# Trampoline_Sensor_Breakout.net
KiCad netlist of a schematic drawn in EAGLE
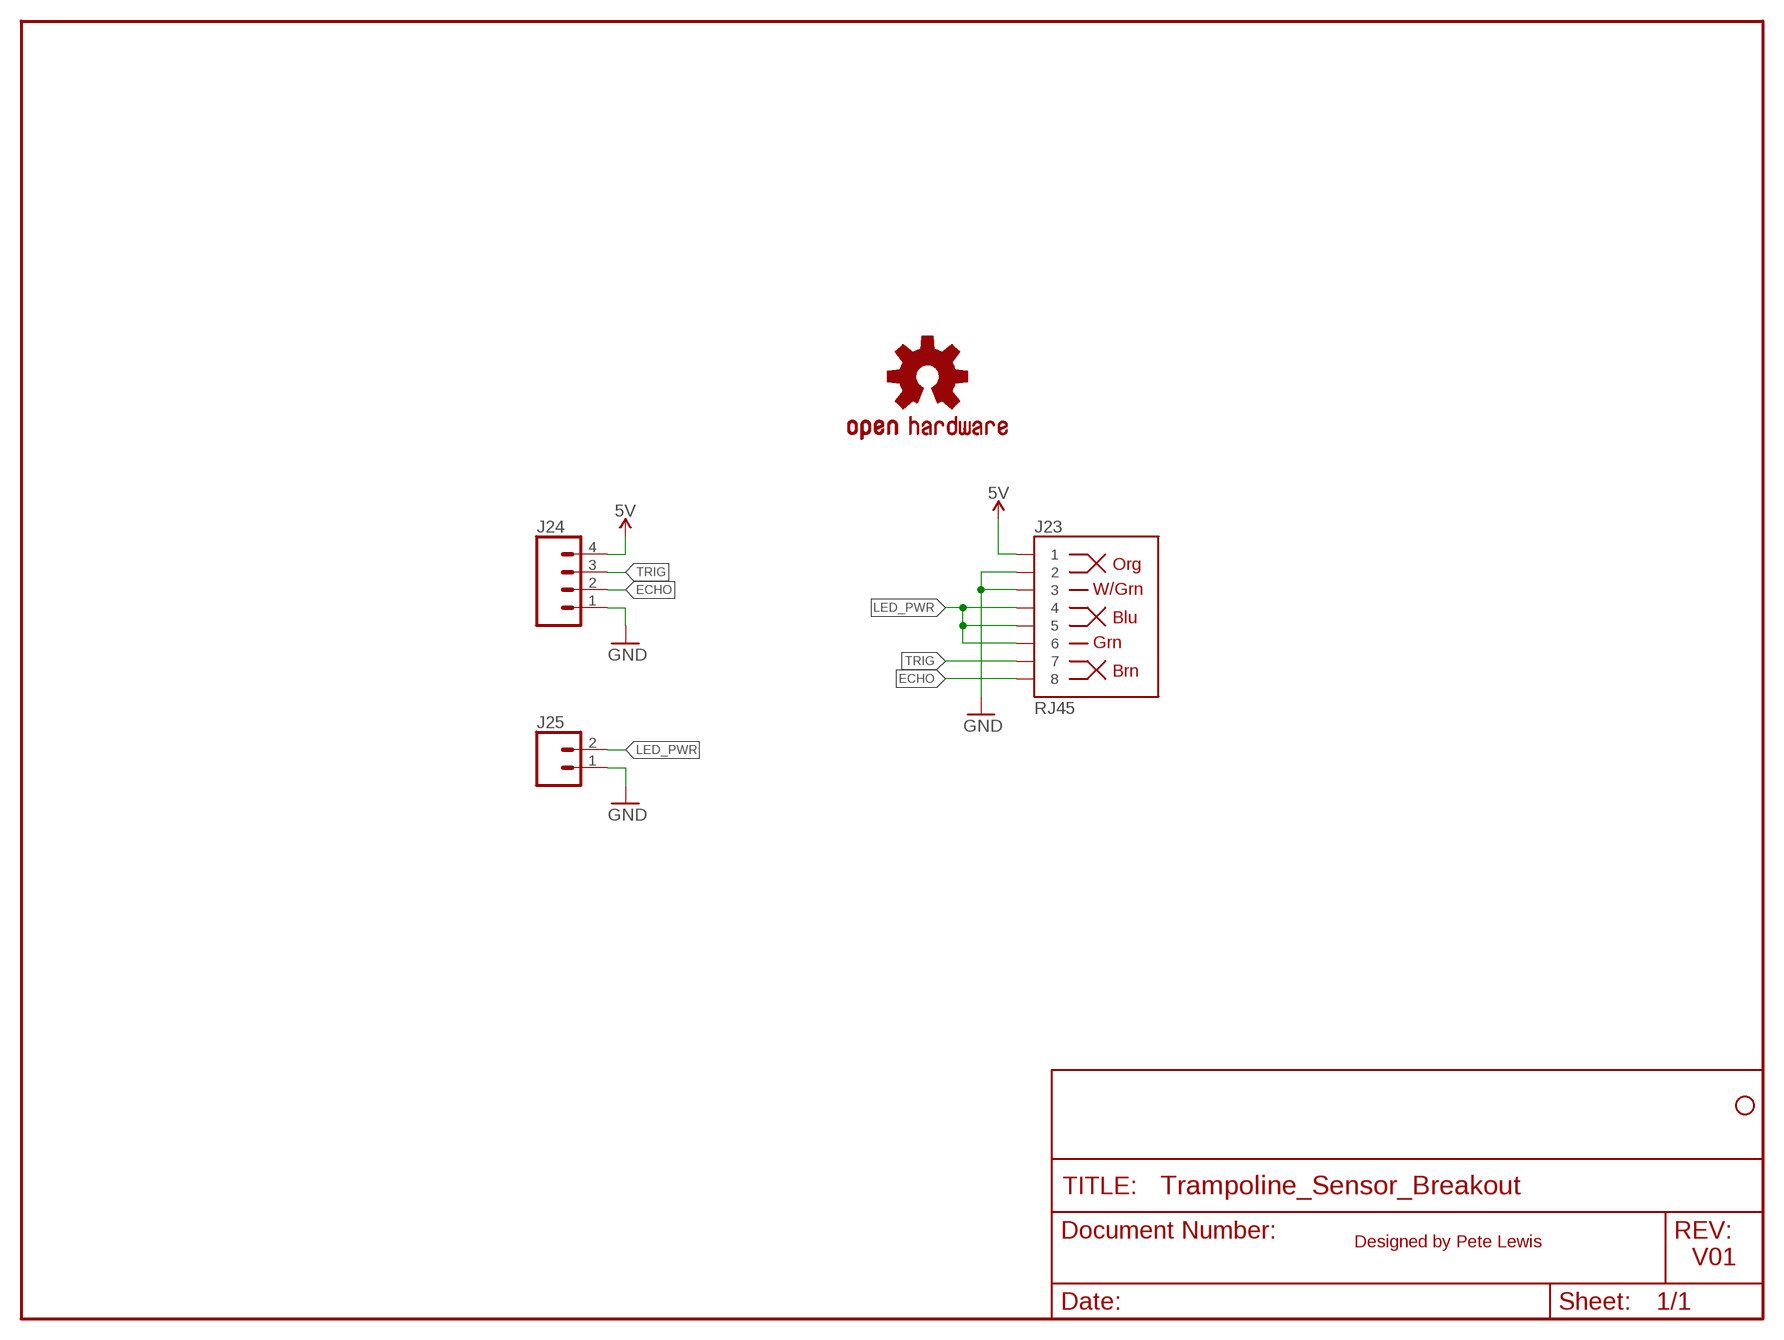
[diagram p0: schematic, sheet 1]

(export (version "E")
  (design (tool "Eeschema 10.0.6"))
  (components
    (comp (ref "J23")
      (value "RJ45")
      (footprint "eagle-import:RJ45-8")
      (libsource (lib "eagle-import") (part "RJ45-8"))
    )
    (comp (ref "J24")
      (value "CONN_04LONGPADS")
      (footprint "eagle-import:1X04_LONGPADS")
      (libsource (lib "eagle-import") (part "CONN_04LONGPADS"))
    )
    (comp (ref "J25")
      (value "CONN_02PTH3")
      (footprint "eagle-import:1X02_LONGPADS")
      (libsource (lib "eagle-import") (part "CONN_02PTH3"))
    )
    (comp (ref "JP8")
      (value "STAND-OFFTIGHTER")
      (footprint "eagle-import:STAND-OFF-TIGHTER")
      (libsource (lib "eagle-import") (part "STAND-OFFTIGHTER"))
    )
    (comp (ref "LOGO2")
      (value "OSHW-LOGOS")
      (footprint "eagle-import:OSHW-LOGO-S")
      (libsource (lib "eagle-import") (part "OSHW-LOGOS"))
    )
  )
  (nets
    (net (code "1") (name "5V") (class "Default")
      (node (ref "J23") (pin "1") (pinfunction "1_1") (pintype "bidirectional"))
      (node (ref "J24") (pin "4") (pinfunction "4_4") (pintype "passive"))
    )
    (net (code "2") (name "ECHO") (class "Default")
      (node (ref "J23") (pin "8") (pinfunction "8_8") (pintype "bidirectional"))
      (node (ref "J24") (pin "2") (pinfunction "2_2") (pintype "passive"))
    )
    (net (code "3") (name "GND") (class "Default")
      (node (ref "J23") (pin "2") (pinfunction "2_2") (pintype "bidirectional"))
      (node (ref "J23") (pin "3") (pinfunction "3_3") (pintype "bidirectional"))
      (node (ref "J24") (pin "1") (pinfunction "1_1") (pintype "passive"))
      (node (ref "J25") (pin "1") (pinfunction "1_1") (pintype "passive"))
    )
    (net (code "4") (name "LED_PWR") (class "Default")
      (node (ref "J23") (pin "4") (pinfunction "4_4") (pintype "bidirectional"))
      (node (ref "J23") (pin "5") (pinfunction "5_5") (pintype "bidirectional"))
      (node (ref "J23") (pin "6") (pinfunction "6_6") (pintype "bidirectional"))
      (node (ref "J25") (pin "2") (pinfunction "2_2") (pintype "passive"))
    )
    (net (code "5") (name "TRIG") (class "Default")
      (node (ref "J23") (pin "7") (pinfunction "7_7") (pintype "bidirectional"))
      (node (ref "J24") (pin "3") (pinfunction "3_3") (pintype "passive"))
    )
  )
)
